# DSP.net
KiCad netlist of a schematic drawn in Altium Designer
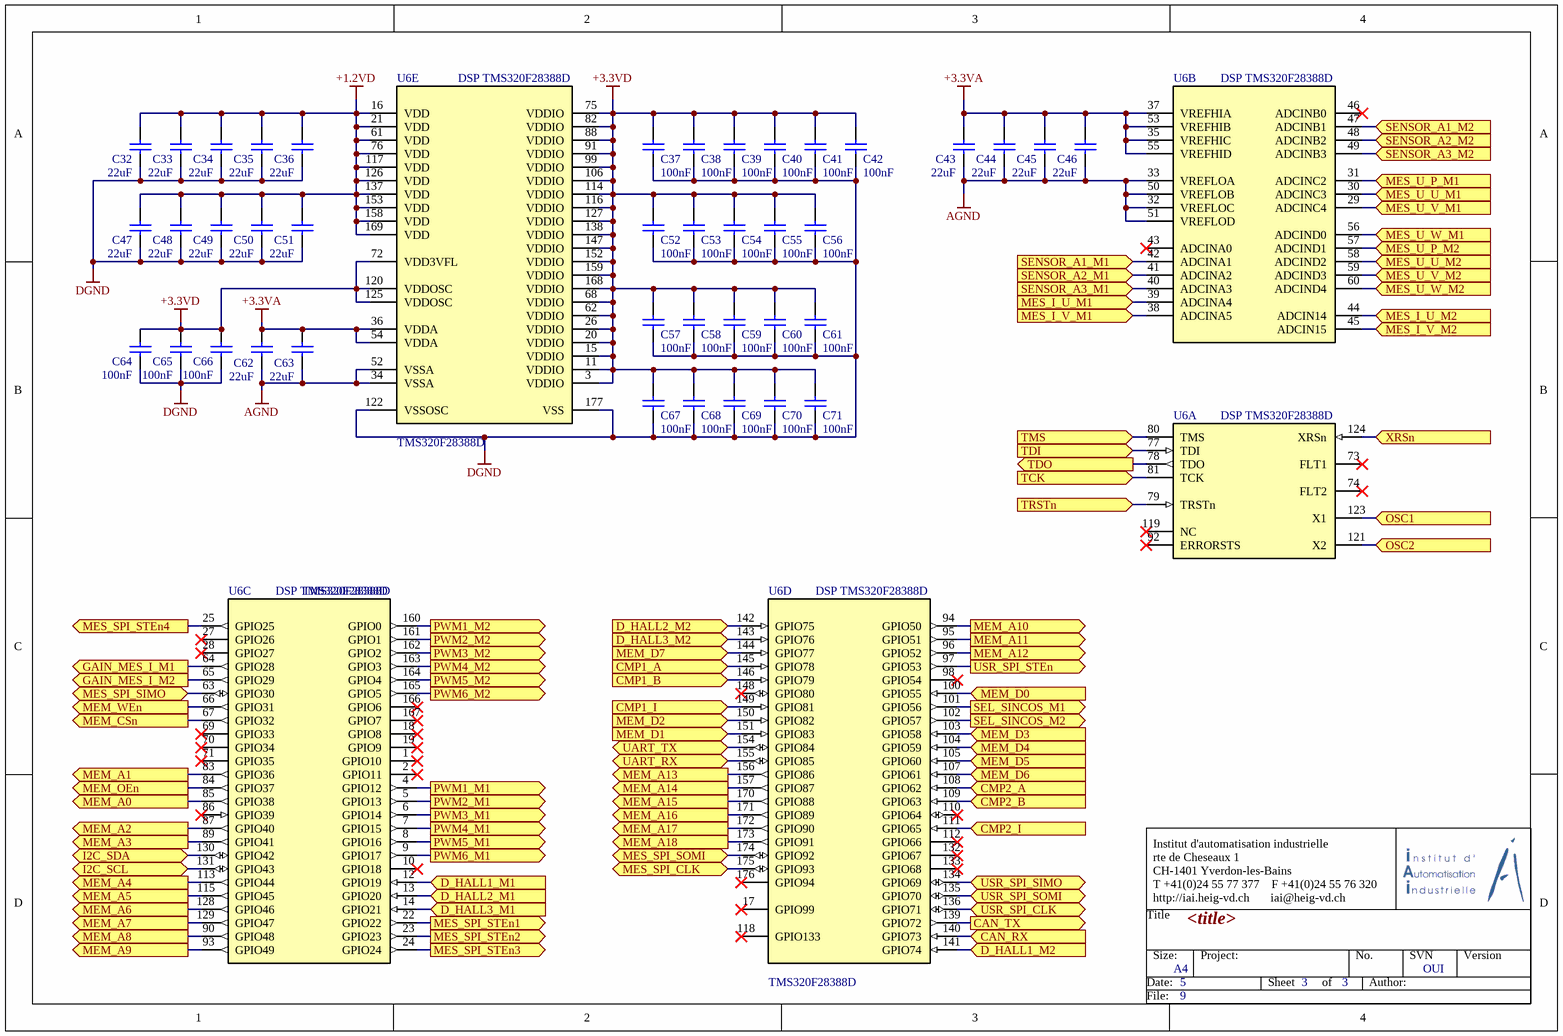
[diagram p0: DSP.SchDoc]

(export (version "E")
  (design (tool "Eeschema 10.0.6"))
  (components
    (comp (ref "C32")
      (value "22uF")
      (footprint "CommandBoard:CAPC1608X08N")
      (description "22µF ±20% 6,3V Condensateurs céramique X5R 0603 (1608 métrique)")
      (fields (field (name "Comment") "CAP CER 22uF 0603"))
      (libsource (lib "CommandBoard") (part "CAP CER 22uF 20% 6V3 0603"))
    )
    (comp (ref "C33")
      (value "22uF")
      (footprint "CommandBoard:CAPC1608X08N")
      (description "22µF ±20% 6,3V Condensateurs céramique X5R 0603 (1608 métrique)")
      (fields (field (name "Comment") "CAP CER 22uF 0603"))
      (libsource (lib "CommandBoard") (part "CAP CER 22uF 20% 6V3 0603"))
    )
    (comp (ref "C34")
      (value "22uF")
      (footprint "CommandBoard:CAPC1608X08N")
      (description "22µF ±20% 6,3V Condensateurs céramique X5R 0603 (1608 métrique)")
      (fields (field (name "Comment") "CAP CER 22uF 0603"))
      (libsource (lib "CommandBoard") (part "CAP CER 22uF 20% 6V3 0603"))
    )
    (comp (ref "C35")
      (value "22uF")
      (footprint "CommandBoard:CAPC1608X08N")
      (description "22µF ±20% 6,3V Condensateurs céramique X5R 0603 (1608 métrique)")
      (fields (field (name "Comment") "CAP CER 22uF 0603"))
      (libsource (lib "CommandBoard") (part "CAP CER 22uF 20% 6V3 0603"))
    )
    (comp (ref "C36")
      (value "22uF")
      (footprint "CommandBoard:CAPC1608X08N")
      (description "22µF ±20% 6,3V Condensateurs céramique X5R 0603 (1608 métrique)")
      (fields (field (name "Comment") "CAP CER 22uF 0603"))
      (libsource (lib "CommandBoard") (part "CAP CER 22uF 20% 6V3 0603"))
    )
    (comp (ref "C37")
      (value "100nF")
      (footprint "CommandBoard:CAPC1608X08N")
      (description "0,1µF ±10% 10V Condensateurs céramique X7R 0603 (1608 métrique)")
      (fields (field (name "Comment") "CAP CER 100nF 0603"))
      (libsource (lib "CommandBoard") (part "CAP CER 100nF 10% 10V 0603"))
    )
    (comp (ref "C38")
      (value "100nF")
      (footprint "CommandBoard:CAPC1608X08N")
      (description "0,1µF ±10% 10V Condensateurs céramique X7R 0603 (1608 métrique)")
      (fields (field (name "Comment") "CAP CER 100nF 0603"))
      (libsource (lib "CommandBoard") (part "CAP CER 100nF 10% 10V 0603"))
    )
    (comp (ref "C39")
      (value "100nF")
      (footprint "CommandBoard:CAPC1608X08N")
      (description "0,1µF ±10% 10V Condensateurs céramique X7R 0603 (1608 métrique)")
      (fields (field (name "Comment") "CAP CER 100nF 0603"))
      (libsource (lib "CommandBoard") (part "CAP CER 100nF 10% 10V 0603"))
    )
    (comp (ref "C40")
      (value "100nF")
      (footprint "CommandBoard:CAPC1608X08N")
      (description "0,1µF ±10% 10V Condensateurs céramique X7R 0603 (1608 métrique)")
      (fields (field (name "Comment") "CAP CER 100nF 0603"))
      (libsource (lib "CommandBoard") (part "CAP CER 100nF 10% 10V 0603"))
    )
    (comp (ref "C41")
      (value "100nF")
      (footprint "CommandBoard:CAPC1608X08N")
      (description "0,1µF ±10% 10V Condensateurs céramique X7R 0603 (1608 métrique)")
      (fields (field (name "Comment") "CAP CER 100nF 0603"))
      (libsource (lib "CommandBoard") (part "CAP CER 100nF 10% 10V 0603"))
    )
    (comp (ref "C42")
      (value "100nF")
      (footprint "CommandBoard:CAPC1608X08N")
      (description "0,1µF ±10% 10V Condensateurs céramique X7R 0603 (1608 métrique)")
      (fields (field (name "Comment") "CAP CER 100nF 0603"))
      (libsource (lib "CommandBoard") (part "CAP CER 100nF 10% 10V 0603"))
    )
    (comp (ref "C43")
      (value "22uF")
      (footprint "CommandBoard:CAPC1608X08N")
      (description "22µF ±20% 6,3V Condensateurs céramique X5R 0603 (1608 métrique)")
      (fields (field (name "Comment") "CAP CER 22uF 0603"))
      (libsource (lib "CommandBoard") (part "CAP CER 22uF 20% 6V3 0603"))
    )
    (comp (ref "C44")
      (value "22uF")
      (footprint "CommandBoard:CAPC1608X08N")
      (description "22µF ±20% 6,3V Condensateurs céramique X5R 0603 (1608 métrique)")
      (fields (field (name "Comment") "CAP CER 22uF 0603"))
      (libsource (lib "CommandBoard") (part "CAP CER 22uF 20% 6V3 0603"))
    )
    (comp (ref "C45")
      (value "22uF")
      (footprint "CommandBoard:CAPC1608X08N")
      (description "22µF ±20% 6,3V Condensateurs céramique X5R 0603 (1608 métrique)")
      (fields (field (name "Comment") "CAP CER 22uF 0603"))
      (libsource (lib "CommandBoard") (part "CAP CER 22uF 20% 6V3 0603"))
    )
    (comp (ref "C46")
      (value "22uF")
      (footprint "CommandBoard:CAPC1608X08N")
      (description "22µF ±20% 6,3V Condensateurs céramique X5R 0603 (1608 métrique)")
      (fields (field (name "Comment") "CAP CER 22uF 0603"))
      (libsource (lib "CommandBoard") (part "CAP CER 22uF 20% 6V3 0603"))
    )
    (comp (ref "C47")
      (value "22uF")
      (footprint "CommandBoard:CAPC1608X08N")
      (description "22µF ±20% 6,3V Condensateurs céramique X5R 0603 (1608 métrique)")
      (fields (field (name "Comment") "CAP CER 22uF 0603"))
      (libsource (lib "CommandBoard") (part "CAP CER 22uF 20% 6V3 0603"))
    )
    (comp (ref "C48")
      (value "22uF")
      (footprint "CommandBoard:CAPC1608X08N")
      (description "22µF ±20% 6,3V Condensateurs céramique X5R 0603 (1608 métrique)")
      (fields (field (name "Comment") "CAP CER 22uF 0603"))
      (libsource (lib "CommandBoard") (part "CAP CER 22uF 20% 6V3 0603"))
    )
    (comp (ref "C49")
      (value "22uF")
      (footprint "CommandBoard:CAPC1608X08N")
      (description "22µF ±20% 6,3V Condensateurs céramique X5R 0603 (1608 métrique)")
      (fields (field (name "Comment") "CAP CER 22uF 0603"))
      (libsource (lib "CommandBoard") (part "CAP CER 22uF 20% 6V3 0603"))
    )
    (comp (ref "C50")
      (value "22uF")
      (footprint "CommandBoard:CAPC1608X08N")
      (description "22µF ±20% 6,3V Condensateurs céramique X5R 0603 (1608 métrique)")
      (fields (field (name "Comment") "CAP CER 22uF 0603"))
      (libsource (lib "CommandBoard") (part "CAP CER 22uF 20% 6V3 0603"))
    )
    (comp (ref "C51")
      (value "22uF")
      (footprint "CommandBoard:CAPC1608X08N")
      (description "22µF ±20% 6,3V Condensateurs céramique X5R 0603 (1608 métrique)")
      (fields (field (name "Comment") "CAP CER 22uF 0603"))
      (libsource (lib "CommandBoard") (part "CAP CER 22uF 20% 6V3 0603"))
    )
    (comp (ref "C52")
      (value "100nF")
      (footprint "CommandBoard:CAPC1608X08N")
      (description "0,1µF ±10% 10V Condensateurs céramique X7R 0603 (1608 métrique)")
      (fields (field (name "Comment") "CAP CER 100nF 0603"))
      (libsource (lib "CommandBoard") (part "CAP CER 100nF 10% 10V 0603"))
    )
    (comp (ref "C53")
      (value "100nF")
      (footprint "CommandBoard:CAPC1608X08N")
      (description "0,1µF ±10% 10V Condensateurs céramique X7R 0603 (1608 métrique)")
      (fields (field (name "Comment") "CAP CER 100nF 0603"))
      (libsource (lib "CommandBoard") (part "CAP CER 100nF 10% 10V 0603"))
    )
    (comp (ref "C54")
      (value "100nF")
      (footprint "CommandBoard:CAPC1608X08N")
      (description "0,1µF ±10% 10V Condensateurs céramique X7R 0603 (1608 métrique)")
      (fields (field (name "Comment") "CAP CER 100nF 0603"))
      (libsource (lib "CommandBoard") (part "CAP CER 100nF 10% 10V 0603"))
    )
    (comp (ref "C55")
      (value "100nF")
      (footprint "CommandBoard:CAPC1608X08N")
      (description "0,1µF ±10% 10V Condensateurs céramique X7R 0603 (1608 métrique)")
      (fields (field (name "Comment") "CAP CER 100nF 0603"))
      (libsource (lib "CommandBoard") (part "CAP CER 100nF 10% 10V 0603"))
    )
    (comp (ref "C56")
      (value "100nF")
      (footprint "CommandBoard:CAPC1608X08N")
      (description "0,1µF ±10% 10V Condensateurs céramique X7R 0603 (1608 métrique)")
      (fields (field (name "Comment") "CAP CER 100nF 0603"))
      (libsource (lib "CommandBoard") (part "CAP CER 100nF 10% 10V 0603"))
    )
    (comp (ref "C57")
      (value "100nF")
      (footprint "CommandBoard:CAPC1608X08N")
      (description "0,1µF ±10% 10V Condensateurs céramique X7R 0603 (1608 métrique)")
      (fields (field (name "Comment") "CAP CER 100nF 0603"))
      (libsource (lib "CommandBoard") (part "CAP CER 100nF 10% 10V 0603"))
    )
    (comp (ref "C58")
      (value "100nF")
      (footprint "CommandBoard:CAPC1608X08N")
      (description "0,1µF ±10% 10V Condensateurs céramique X7R 0603 (1608 métrique)")
      (fields (field (name "Comment") "CAP CER 100nF 0603"))
      (libsource (lib "CommandBoard") (part "CAP CER 100nF 10% 10V 0603"))
    )
    (comp (ref "C59")
      (value "100nF")
      (footprint "CommandBoard:CAPC1608X08N")
      (description "0,1µF ±10% 10V Condensateurs céramique X7R 0603 (1608 métrique)")
      (fields (field (name "Comment") "CAP CER 100nF 0603"))
      (libsource (lib "CommandBoard") (part "CAP CER 100nF 10% 10V 0603"))
    )
    (comp (ref "C60")
      (value "100nF")
      (footprint "CommandBoard:CAPC1608X08N")
      (description "0,1µF ±10% 10V Condensateurs céramique X7R 0603 (1608 métrique)")
      (fields (field (name "Comment") "CAP CER 100nF 0603"))
      (libsource (lib "CommandBoard") (part "CAP CER 100nF 10% 10V 0603"))
    )
    (comp (ref "C61")
      (value "100nF")
      (footprint "CommandBoard:CAPC1608X08N")
      (description "0,1µF ±10% 10V Condensateurs céramique X7R 0603 (1608 métrique)")
      (fields (field (name "Comment") "CAP CER 100nF 0603"))
      (libsource (lib "CommandBoard") (part "CAP CER 100nF 10% 10V 0603"))
    )
    (comp (ref "C62")
      (value "22uF")
      (footprint "CommandBoard:CAPC1608X08N")
      (description "22µF ±20% 6,3V Condensateurs céramique X5R 0603 (1608 métrique)")
      (fields (field (name "Comment") "CAP CER 22uF 0603"))
      (libsource (lib "CommandBoard") (part "CAP CER 22uF 20% 6V3 0603"))
    )
    (comp (ref "C63")
      (value "22uF")
      (footprint "CommandBoard:CAPC1608X08N")
      (description "22µF ±20% 6,3V Condensateurs céramique X5R 0603 (1608 métrique)")
      (fields (field (name "Comment") "CAP CER 22uF 0603"))
      (libsource (lib "CommandBoard") (part "CAP CER 22uF 20% 6V3 0603"))
    )
    (comp (ref "C64")
      (value "100nF")
      (footprint "CommandBoard:CAPC1608X08N")
      (description "0,1µF ±10% 10V Condensateurs céramique X7R 0603 (1608 métrique)")
      (fields (field (name "Comment") "CAP CER 100nF 0603"))
      (libsource (lib "CommandBoard") (part "CAP CER 100nF 10% 10V 0603"))
    )
    (comp (ref "C65")
      (value "100nF")
      (footprint "CommandBoard:CAPC1608X08N")
      (description "0,1µF ±10% 10V Condensateurs céramique X7R 0603 (1608 métrique)")
      (fields (field (name "Comment") "CAP CER 100nF 0603"))
      (libsource (lib "CommandBoard") (part "CAP CER 100nF 10% 10V 0603"))
    )
    (comp (ref "C66")
      (value "100nF")
      (footprint "CommandBoard:CAPC1608X08N")
      (description "0,1µF ±10% 10V Condensateurs céramique X7R 0603 (1608 métrique)")
      (fields (field (name "Comment") "CAP CER 100nF 0603"))
      (libsource (lib "CommandBoard") (part "CAP CER 100nF 10% 10V 0603"))
    )
    (comp (ref "C67")
      (value "100nF")
      (footprint "CommandBoard:CAPC1608X08N")
      (description "0,1µF ±10% 10V Condensateurs céramique X7R 0603 (1608 métrique)")
      (fields (field (name "Comment") "CAP CER 100nF 0603"))
      (libsource (lib "CommandBoard") (part "CAP CER 100nF 10% 10V 0603"))
    )
    (comp (ref "C68")
      (value "100nF")
      (footprint "CommandBoard:CAPC1608X08N")
      (description "0,1µF ±10% 10V Condensateurs céramique X7R 0603 (1608 métrique)")
      (fields (field (name "Comment") "CAP CER 100nF 0603"))
      (libsource (lib "CommandBoard") (part "CAP CER 100nF 10% 10V 0603"))
    )
    (comp (ref "C69")
      (value "100nF")
      (footprint "CommandBoard:CAPC1608X08N")
      (description "0,1µF ±10% 10V Condensateurs céramique X7R 0603 (1608 métrique)")
      (fields (field (name "Comment") "CAP CER 100nF 0603"))
      (libsource (lib "CommandBoard") (part "CAP CER 100nF 10% 10V 0603"))
    )
    (comp (ref "C70")
      (value "100nF")
      (footprint "CommandBoard:CAPC1608X08N")
      (description "0,1µF ±10% 10V Condensateurs céramique X7R 0603 (1608 métrique)")
      (fields (field (name "Comment") "CAP CER 100nF 0603"))
      (libsource (lib "CommandBoard") (part "CAP CER 100nF 10% 10V 0603"))
    )
    (comp (ref "C71")
      (value "100nF")
      (footprint "CommandBoard:CAPC1608X08N")
      (description "0,1µF ±10% 10V Condensateurs céramique X7R 0603 (1608 métrique)")
      (fields (field (name "Comment") "CAP CER 100nF 0603"))
      (libsource (lib "CommandBoard") (part "CAP CER 100nF 10% 10V 0603"))
    )
    (comp (ref "U6")
      (value "DSP TMS320F28388D")
      (footprint "CommandBoard:TSQFP50P2600X2600X160_HS-177N")
      (fields (field (name "ALTIUM_VALUE") "TMS320F28388D"))
      (libsource (lib "") (part "DSP TMS320F28388D_2"))
    )
  )
  (nets
    (net (code "1") (name "+1.2VD") (class "Default")
      (node (ref "C32") (pin "2") (pinfunction "2_2") (pintype "passive"))
      (node (ref "C33") (pin "2") (pinfunction "2_2") (pintype "passive"))
      (node (ref "C34") (pin "2") (pinfunction "2_2") (pintype "passive"))
      (node (ref "C35") (pin "2") (pinfunction "2_2") (pintype "passive"))
      (node (ref "C36") (pin "2") (pinfunction "2_2") (pintype "passive"))
      (node (ref "C47") (pin "2") (pinfunction "2_2") (pintype "passive"))
      (node (ref "C48") (pin "2") (pinfunction "2_2") (pintype "passive"))
      (node (ref "C49") (pin "2") (pinfunction "2_2") (pintype "passive"))
      (node (ref "C50") (pin "2") (pinfunction "2_2") (pintype "passive"))
      (node (ref "C51") (pin "2") (pinfunction "2_2") (pintype "passive"))
      (node (ref "U6") (pin "117") (pinfunction "VDD_117") (pintype "power_in"))
      (node (ref "U6") (pin "126") (pinfunction "VDD_126") (pintype "power_in"))
      (node (ref "U6") (pin "137") (pinfunction "VDD_137") (pintype "power_in"))
      (node (ref "U6") (pin "153") (pinfunction "VDD_153") (pintype "power_in"))
      (node (ref "U6") (pin "158") (pinfunction "VDD_158") (pintype "power_in"))
      (node (ref "U6") (pin "16") (pinfunction "VDD_16") (pintype "power_in"))
      (node (ref "U6") (pin "169") (pinfunction "VDD_169") (pintype "power_in"))
      (node (ref "U6") (pin "21") (pinfunction "VDD_21") (pintype "power_in"))
      (node (ref "U6") (pin "61") (pinfunction "VDD_61") (pintype "power_in"))
      (node (ref "U6") (pin "76") (pinfunction "VDD_76") (pintype "power_in"))
    )
    (net (code "2") (name "+3.3VA") (class "Default")
      (node (ref "C43") (pin "2") (pinfunction "2_2") (pintype "passive"))
      (node (ref "C44") (pin "2") (pinfunction "2_2") (pintype "passive"))
      (node (ref "C45") (pin "2") (pinfunction "2_2") (pintype "passive"))
      (node (ref "C46") (pin "2") (pinfunction "2_2") (pintype "passive"))
      (node (ref "C62") (pin "2") (pinfunction "2_2") (pintype "passive"))
      (node (ref "C63") (pin "2") (pinfunction "2_2") (pintype "passive"))
      (node (ref "U6") (pin "35") (pinfunction "VREFHIC_35") (pintype "power_in"))
      (node (ref "U6") (pin "36") (pinfunction "VDDA_36") (pintype "power_in"))
      (node (ref "U6") (pin "37") (pinfunction "VREFHIA_37") (pintype "power_in"))
      (node (ref "U6") (pin "53") (pinfunction "VREFHIB_53") (pintype "power_in"))
      (node (ref "U6") (pin "54") (pinfunction "VDDA_54") (pintype "power_in"))
      (node (ref "U6") (pin "55") (pinfunction "VREFHID_55") (pintype "power_in"))
    )
    (net (code "3") (name "+3.3VD") (class "Default")
      (node (ref "C37") (pin "2") (pinfunction "2_2") (pintype "passive"))
      (node (ref "C38") (pin "2") (pinfunction "2_2") (pintype "passive"))
      (node (ref "C39") (pin "2") (pinfunction "2_2") (pintype "passive"))
      (node (ref "C40") (pin "2") (pinfunction "2_2") (pintype "passive"))
      (node (ref "C41") (pin "2") (pinfunction "2_2") (pintype "passive"))
      (node (ref "C42") (pin "2") (pinfunction "2_2") (pintype "passive"))
      (node (ref "C52") (pin "2") (pinfunction "2_2") (pintype "passive"))
      (node (ref "C53") (pin "2") (pinfunction "2_2") (pintype "passive"))
      (node (ref "C54") (pin "2") (pinfunction "2_2") (pintype "passive"))
      (node (ref "C55") (pin "2") (pinfunction "2_2") (pintype "passive"))
      (node (ref "C56") (pin "2") (pinfunction "2_2") (pintype "passive"))
      (node (ref "C57") (pin "2") (pinfunction "2_2") (pintype "passive"))
      (node (ref "C58") (pin "2") (pinfunction "2_2") (pintype "passive"))
      (node (ref "C59") (pin "2") (pinfunction "2_2") (pintype "passive"))
      (node (ref "C60") (pin "2") (pinfunction "2_2") (pintype "passive"))
      (node (ref "C61") (pin "2") (pinfunction "2_2") (pintype "passive"))
      (node (ref "C64") (pin "2") (pinfunction "2_2") (pintype "passive"))
      (node (ref "C65") (pin "2") (pinfunction "2_2") (pintype "passive"))
      (node (ref "C66") (pin "2") (pinfunction "2_2") (pintype "passive"))
      (node (ref "C67") (pin "2") (pinfunction "2_2") (pintype "passive"))
      (node (ref "C68") (pin "2") (pinfunction "2_2") (pintype "passive"))
      (node (ref "C69") (pin "2") (pinfunction "2_2") (pintype "passive"))
      (node (ref "C70") (pin "2") (pinfunction "2_2") (pintype "passive"))
      (node (ref "C71") (pin "2") (pinfunction "2_2") (pintype "passive"))
      (node (ref "U6") (pin "106") (pinfunction "VDDIO_106") (pintype "power_in"))
      (node (ref "U6") (pin "11") (pinfunction "VDDIO_11") (pintype "power_in"))
      (node (ref "U6") (pin "114") (pinfunction "VDDIO_114") (pintype "power_in"))
      (node (ref "U6") (pin "116") (pinfunction "VDDIO_116") (pintype "power_in"))
      (node (ref "U6") (pin "120") (pinfunction "VDDOSC_120") (pintype "power_in"))
      (node (ref "U6") (pin "125") (pinfunction "VDDOSC_125") (pintype "power_in"))
      (node (ref "U6") (pin "127") (pinfunction "VDDIO_127") (pintype "power_in"))
      (node (ref "U6") (pin "138") (pinfunction "VDDIO_138") (pintype "power_in"))
      (node (ref "U6") (pin "147") (pinfunction "VDDIO_147") (pintype "power_in"))
      (node (ref "U6") (pin "15") (pinfunction "VDDIO_15") (pintype "power_in"))
      (node (ref "U6") (pin "152") (pinfunction "VDDIO_152") (pintype "power_in"))
      (node (ref "U6") (pin "159") (pinfunction "VDDIO_159") (pintype "power_in"))
      (node (ref "U6") (pin "168") (pinfunction "VDDIO_168") (pintype "power_in"))
      (node (ref "U6") (pin "20") (pinfunction "VDDIO_20") (pintype "power_in"))
      (node (ref "U6") (pin "26") (pinfunction "VDDIO_26") (pintype "power_in"))
      (node (ref "U6") (pin "3") (pinfunction "VDDIO_3") (pintype "power_in"))
      (node (ref "U6") (pin "62") (pinfunction "VDDIO_62") (pintype "power_in"))
      (node (ref "U6") (pin "68") (pinfunction "VDDIO_68") (pintype "power_in"))
      (node (ref "U6") (pin "72") (pinfunction "VDD3VFL_72") (pintype "power_in"))
      (node (ref "U6") (pin "75") (pinfunction "VDDIO_75") (pintype "power_in"))
      (node (ref "U6") (pin "82") (pinfunction "VDDIO_82") (pintype "power_in"))
      (node (ref "U6") (pin "88") (pinfunction "VDDIO_88") (pintype "power_in"))
      (node (ref "U6") (pin "91") (pinfunction "VDDIO_91") (pintype "power_in"))
      (node (ref "U6") (pin "99") (pinfunction "VDDIO_99") (pintype "power_in"))
    )
    (net (code "4") (name "/CAN_RX") (class "Default")
      (node (ref "U6") (pin "140") (pinfunction "GPIO73_140") (pintype "input"))
    )
    (net (code "5") (name "/CAN_TX") (class "Default")
      (node (ref "U6") (pin "139") (pinfunction "GPIO72_139") (pintype "output"))
    )
    (net (code "6") (name "/CMP1_A") (class "Default")
      (node (ref "U6") (pin "145") (pinfunction "GPIO78_145") (pintype "input"))
    )
    (net (code "7") (name "/CMP1_B") (class "Default")
      (node (ref "U6") (pin "146") (pinfunction "GPIO79_146") (pintype "input"))
    )
    (net (code "8") (name "/CMP1_I") (class "Default")
      (node (ref "U6") (pin "149") (pinfunction "GPIO81_149") (pintype "input"))
    )
    (net (code "9") (name "/CMP2_A") (class "Default")
      (node (ref "U6") (pin "108") (pinfunction "GPIO62_108") (pintype "input"))
    )
    (net (code "10") (name "/CMP2_B") (class "Default")
      (node (ref "U6") (pin "109") (pinfunction "GPIO63_109") (pintype "input"))
    )
    (net (code "11") (name "/CMP2_I") (class "Default")
      (node (ref "U6") (pin "111") (pinfunction "GPIO65_111") (pintype "input"))
    )
    (net (code "12") (name "/D_HALL1_M1") (class "Default")
      (node (ref "U6") (pin "12") (pinfunction "GPIO19_12") (pintype "input"))
    )
    (net (code "13") (name "/D_HALL1_M2") (class "Default")
      (node (ref "U6") (pin "141") (pinfunction "GPIO74_141") (pintype "input"))
    )
    (net (code "14") (name "/D_HALL2_M1") (class "Default")
      (node (ref "U6") (pin "13") (pinfunction "GPIO20_13") (pintype "input"))
    )
    (net (code "15") (name "/D_HALL2_M2") (class "Default")
      (node (ref "U6") (pin "142") (pinfunction "GPIO75_142") (pintype "input"))
    )
    (net (code "16") (name "/D_HALL3_M1") (class "Default")
      (node (ref "U6") (pin "14") (pinfunction "GPIO21_14") (pintype "input"))
    )
    (net (code "17") (name "/D_HALL3_M2") (class "Default")
      (node (ref "U6") (pin "143") (pinfunction "GPIO76_143") (pintype "input"))
    )
    (net (code "18") (name "/GAIN_MES_I_M1") (class "Default")
      (node (ref "U6") (pin "64") (pinfunction "GPIO28_64") (pintype "output"))
    )
    (net (code "19") (name "/GAIN_MES_I_M2") (class "Default")
      (node (ref "U6") (pin "65") (pinfunction "GPIO29_65") (pintype "output"))
    )
    (net (code "20") (name "/I2C_SCL") (class "Default")
      (node (ref "U6") (pin "131") (pinfunction "GPIO43_131") (pintype "bidirectional"))
    )
    (net (code "21") (name "/I2C_SDA") (class "Default")
      (node (ref "U6") (pin "130") (pinfunction "GPIO42_130") (pintype "bidirectional"))
    )
    (net (code "22") (name "/MEM_A0") (class "Default")
      (node (ref "U6") (pin "85") (pinfunction "GPIO38_85") (pintype "output"))
    )
    (net (code "23") (name "/MEM_A1") (class "Default")
      (node (ref "U6") (pin "83") (pinfunction "GPIO36_83") (pintype "output"))
    )
    (net (code "24") (name "/MEM_A2") (class "Default")
      (node (ref "U6") (pin "87") (pinfunction "GPIO40_87") (pintype "output"))
    )
    (net (code "25") (name "/MEM_A3") (class "Default")
      (node (ref "U6") (pin "89") (pinfunction "GPIO41_89") (pintype "output"))
    )
    (net (code "26") (name "/MEM_A4") (class "Default")
      (node (ref "U6") (pin "113") (pinfunction "GPIO44_113") (pintype "output"))
    )
    (net (code "27") (name "/MEM_A5") (class "Default")
      (node (ref "U6") (pin "115") (pinfunction "GPIO45_115") (pintype "output"))
    )
    (net (code "28") (name "/MEM_A6") (class "Default")
      (node (ref "U6") (pin "128") (pinfunction "GPIO46_128") (pintype "output"))
    )
    (net (code "29") (name "/MEM_A7") (class "Default")
      (node (ref "U6") (pin "129") (pinfunction "GPIO47_129") (pintype "output"))
    )
    (net (code "30") (name "/MEM_A8") (class "Default")
      (node (ref "U6") (pin "90") (pinfunction "GPIO48_90") (pintype "output"))
    )
    (net (code "31") (name "/MEM_A9") (class "Default")
      (node (ref "U6") (pin "93") (pinfunction "GPIO49_93") (pintype "output"))
    )
    (net (code "32") (name "/MEM_A10") (class "Default")
      (node (ref "U6") (pin "94") (pinfunction "GPIO50_94") (pintype "output"))
    )
    (net (code "33") (name "/MEM_A11") (class "Default")
      (node (ref "U6") (pin "95") (pinfunction "GPIO51_95") (pintype "output"))
    )
    (net (code "34") (name "/MEM_A12") (class "Default")
      (node (ref "U6") (pin "96") (pinfunction "GPIO52_96") (pintype "output"))
    )
    (net (code "35") (name "/MEM_A13") (class "Default")
      (node (ref "U6") (pin "156") (pinfunction "GPIO86_156") (pintype "output"))
    )
    (net (code "36") (name "/MEM_A14") (class "Default")
      (node (ref "U6") (pin "157") (pinfunction "GPIO87_157") (pintype "output"))
    )
    (net (code "37") (name "/MEM_A15") (class "Default")
      (node (ref "U6") (pin "170") (pinfunction "GPIO88_170") (pintype "output"))
    )
    (net (code "38") (name "/MEM_A16") (class "Default")
      (node (ref "U6") (pin "171") (pinfunction "GPIO89_171") (pintype "output"))
    )
    (net (code "39") (name "/MEM_A17") (class "Default")
      (node (ref "U6") (pin "172") (pinfunction "GPIO90_172") (pintype "output"))
    )
    (net (code "40") (name "/MEM_A18") (class "Default")
      (node (ref "U6") (pin "173") (pinfunction "GPIO91_173") (pintype "output"))
    )
    (net (code "41") (name "/MEM_CSn") (class "Default")
      (node (ref "U6") (pin "67") (pinfunction "GPIO32_67") (pintype "output"))
    )
    (net (code "42") (name "/MEM_D0") (class "Default")
      (node (ref "U6") (pin "100") (pinfunction "GPIO55_100") (pintype "input"))
    )
    (net (code "43") (name "/MEM_D1") (class "Default")
      (node (ref "U6") (pin "151") (pinfunction "GPIO83_151") (pintype "input"))
    )
    (net (code "44") (name "/MEM_D2") (class "Default")
      (node (ref "U6") (pin "150") (pinfunction "GPIO82_150") (pintype "input"))
    )
    (net (code "45") (name "/MEM_D3") (class "Default")
      (node (ref "U6") (pin "103") (pinfunction "GPIO58_103") (pintype "input"))
    )
    (net (code "46") (name "/MEM_D4") (class "Default")
      (node (ref "U6") (pin "104") (pinfunction "GPIO59_104") (pintype "input"))
    )
    (net (code "47") (name "/MEM_D5") (class "Default")
      (node (ref "U6") (pin "105") (pinfunction "GPIO60_105") (pintype "input"))
    )
    (net (code "48") (name "/MEM_D6") (class "Default")
      (node (ref "U6") (pin "107") (pinfunction "GPIO61_107") (pintype "input"))
    )
    (net (code "49") (name "/MEM_D7") (class "Default")
      (node (ref "U6") (pin "144") (pinfunction "GPIO77_144") (pintype "input"))
    )
    (net (code "50") (name "/MEM_OEn") (class "Default")
      (node (ref "U6") (pin "84") (pinfunction "GPIO37_84") (pintype "output"))
    )
    (net (code "51") (name "/MEM_WEn") (class "Default")
      (node (ref "U6") (pin "66") (pinfunction "GPIO31_66") (pintype "output"))
    )
    (net (code "52") (name "/MES_I_U_M1") (class "Default")
      (node (ref "U6") (pin "39") (pinfunction "ADCINA4_39") (pintype "passive"))
    )
    (net (code "53") (name "/MES_I_U_M2") (class "Default")
      (node (ref "U6") (pin "44") (pinfunction "ADCIN14_44") (pintype "passive"))
    )
    (net (code "54") (name "/MES_I_V_M1") (class "Default")
      (node (ref "U6") (pin "38") (pinfunction "ADCINA5_38") (pintype "passive"))
    )
    (net (code "55") (name "/MES_I_V_M2") (class "Default")
      (node (ref "U6") (pin "45") (pinfunction "ADCIN15_45") (pintype "passive"))
    )
    (net (code "56") (name "/MES_SPI_CLK") (class "Default")
      (node (ref "U6") (pin "175") (pinfunction "GPIO93_175") (pintype "bidirectional"))
    )
    (net (code "57") (name "/MES_SPI_SIMO") (class "Default")
      (node (ref "U6") (pin "63") (pinfunction "GPIO30_63") (pintype "bidirectional"))
    )
    (net (code "58") (name "/MES_SPI_SOMI") (class "Default")
      (node (ref "U6") (pin "174") (pinfunction "GPIO92_174") (pintype "bidirectional"))
    )
    (net (code "59") (name "/MES_SPI_STEn1") (class "Default")
      (node (ref "U6") (pin "22") (pinfunction "GPIO22_22") (pintype "output"))
    )
    (net (code "60") (name "/MES_SPI_STEn2") (class "Default")
      (node (ref "U6") (pin "23") (pinfunction "GPIO23_23") (pintype "output"))
    )
    (net (code "61") (name "/MES_SPI_STEn3") (class "Default")
      (node (ref "U6") (pin "24") (pinfunction "GPIO24_24") (pintype "output"))
    )
    (net (code "62") (name "/MES_SPI_STEn4") (class "Default")
      (node (ref "U6") (pin "25") (pinfunction "GPIO25_25") (pintype "output"))
    )
    (net (code "63") (name "/MES_U_P_M1") (class "Default")
      (node (ref "U6") (pin "31") (pinfunction "ADCINC2_31") (pintype "passive"))
    )
    (net (code "64") (name "/MES_U_P_M2") (class "Default")
      (node (ref "U6") (pin "57") (pinfunction "ADCIND1_57") (pintype "passive"))
    )
    (net (code "65") (name "/MES_U_U_M1") (class "Default")
      (node (ref "U6") (pin "30") (pinfunction "ADCINC3_30") (pintype "passive"))
    )
    (net (code "66") (name "/MES_U_U_M2") (class "Default")
      (node (ref "U6") (pin "58") (pinfunction "ADCIND2_58") (pintype "passive"))
    )
    (net (code "67") (name "/MES_U_V_M1") (class "Default")
      (node (ref "U6") (pin "29") (pinfunction "ADCINC4_29") (pintype "passive"))
    )
    (net (code "68") (name "/MES_U_V_M2") (class "Default")
      (node (ref "U6") (pin "59") (pinfunction "ADCIND3_59") (pintype "passive"))
    )
    (net (code "69") (name "/MES_U_W_M1") (class "Default")
      (node (ref "U6") (pin "56") (pinfunction "ADCIND0_56") (pintype "passive"))
    )
    (net (code "70") (name "/MES_U_W_M2") (class "Default")
      (node (ref "U6") (pin "60") (pinfunction "ADCIND4_60") (pintype "passive"))
    )
    (net (code "71") (name "/OSC1") (class "Default")
      (node (ref "U6") (pin "123") (pinfunction "X1_123") (pintype "passive"))
    )
    (net (code "72") (name "/OSC2") (class "Default")
      (node (ref "U6") (pin "121") (pinfunction "X2_121") (pintype "passive"))
    )
    (net (code "73") (name "/PWM1_M1") (class "Default")
      (node (ref "U6") (pin "4") (pinfunction "GPIO12_4") (pintype "output"))
    )
    (net (code "74") (name "/PWM1_M2") (class "Default")
      (node (ref "U6") (pin "160") (pinfunction "GPIO0_160") (pintype "output"))
    )
    (net (code "75") (name "/PWM2_M1") (class "Default")
      (node (ref "U6") (pin "5") (pinfunction "GPIO13_5") (pintype "output"))
    )
    (net (code "76") (name "/PWM2_M2") (class "Default")
      (node (ref "U6") (pin "161") (pinfunction "GPIO1_161") (pintype "output"))
    )
    (net (code "77") (name "/PWM3_M1") (class "Default")
      (node (ref "U6") (pin "6") (pinfunction "GPIO14_6") (pintype "output"))
    )
    (net (code "78") (name "/PWM3_M2") (class "Default")
      (node (ref "U6") (pin "162") (pinfunction "GPIO2_162") (pintype "output"))
    )
    (net (code "79") (name "/PWM4_M1") (class "Default")
      (node (ref "U6") (pin "7") (pinfunction "GPIO15_7") (pintype "output"))
    )
    (net (code "80") (name "/PWM4_M2") (class "Default")
      (node (ref "U6") (pin "163") (pinfunction "GPIO3_163") (pintype "output"))
    )
    (net (code "81") (name "/PWM5_M1") (class "Default")
      (node (ref "U6") (pin "8") (pinfunction "GPIO16_8") (pintype "output"))
    )
    (net (code "82") (name "/PWM5_M2") (class "Default")
      (node (ref "U6") (pin "164") (pinfunction "GPIO4_164") (pintype "output"))
    )
    (net (code "83") (name "/PWM6_M1") (class "Default")
      (node (ref "U6") (pin "9") (pinfunction "GPIO17_9") (pintype "output"))
    )
    (net (code "84") (name "/PWM6_M2") (class "Default")
      (node (ref "U6") (pin "165") (pinfunction "GPIO5_165") (pintype "output"))
    )
    (net (code "85") (name "/SEL_SINCOS_M1") (class "Default")
      (node (ref "U6") (pin "101") (pinfunction "GPIO56_101") (pintype "output"))
    )
    (net (code "86") (name "/SEL_SINCOS_M2") (class "Default")
      (node (ref "U6") (pin "102") (pinfunction "GPIO57_102") (pintype "output"))
    )
    (net (code "87") (name "/SENSOR_A1_M1") (class "Default")
      (node (ref "U6") (pin "42") (pinfunction "ADCINA1_42") (pintype "passive"))
    )
    (net (code "88") (name "/SENSOR_A1_M2") (class "Default")
      (node (ref "U6") (pin "47") (pinfunction "ADCINB1_47") (pintype "passive"))
    )
    (net (code "89") (name "/SENSOR_A2_M1") (class "Default")
      (node (ref "U6") (pin "41") (pinfunction "ADCINA2_41") (pintype "passive"))
    )
    (net (code "90") (name "/SENSOR_A2_M2") (class "Default")
      (node (ref "U6") (pin "48") (pinfunction "ADCINB2_48") (pintype "passive"))
    )
    (net (code "91") (name "/SENSOR_A3_M1") (class "Default")
      (node (ref "U6") (pin "40") (pinfunction "ADCINA3_40") (pintype "passive"))
    )
    (net (code "92") (name "/SENSOR_A3_M2") (class "Default")
      (node (ref "U6") (pin "49") (pinfunction "ADCINB3_49") (pintype "passive"))
    )
    (net (code "93") (name "/TCK") (class "Default")
      (node (ref "U6") (pin "81") (pinfunction "TCK_81") (pintype "passive"))
    )
    (net (code "94") (name "/TDI") (class "Default")
      (node (ref "U6") (pin "77") (pinfunction "TDI_77") (pintype "input"))
    )
    (net (code "95") (name "/TDO") (class "Default")
      (node (ref "U6") (pin "78") (pinfunction "TDO_78") (pintype "output"))
    )
    (net (code "96") (name "/TMS") (class "Default")
      (node (ref "U6") (pin "80") (pinfunction "TMS_80") (pintype "passive"))
    )
    (net (code "97") (name "/TRSTn") (class "Default")
      (node (ref "U6") (pin "79") (pinfunction "TRST_N_79") (pintype "input"))
    )
    (net (code "98") (name "/UART_RX") (class "Default")
      (node (ref "U6") (pin "155") (pinfunction "GPIO85_155") (pintype "bidirectional"))
    )
    (net (code "99") (name "/UART_TX") (class "Default")
      (node (ref "U6") (pin "154") (pinfunction "GPIO84_154") (pintype "bidirectional"))
    )
    (net (code "100") (name "/USR_SPI_CLK") (class "Default")
      (node (ref "U6") (pin "136") (pinfunction "GPIO71_136") (pintype "bidirectional"))
    )
    (net (code "101") (name "/USR_SPI_SIMO") (class "Default")
      (node (ref "U6") (pin "134") (pinfunction "GPIO69_134") (pintype "bidirectional"))
    )
    (net (code "102") (name "/USR_SPI_SOMI") (class "Default")
      (node (ref "U6") (pin "135") (pinfunction "GPIO70_135") (pintype "bidirectional"))
    )
    (net (code "103") (name "/USR_SPI_STEn") (class "Default")
      (node (ref "U6") (pin "97") (pinfunction "GPIO53_97") (pintype "output"))
    )
    (net (code "104") (name "/XRSn") (class "Default")
      (node (ref "U6") (pin "124") (pinfunction "XRS_N_124") (pintype "input"))
    )
    (net (code "105") (name "AGND") (class "Default")
      (node (ref "C43") (pin "1") (pinfunction "1_1") (pintype "passive"))
      (node (ref "C44") (pin "1") (pinfunction "1_1") (pintype "passive"))
      (node (ref "C45") (pin "1") (pinfunction "1_1") (pintype "passive"))
      (node (ref "C46") (pin "1") (pinfunction "1_1") (pintype "passive"))
      (node (ref "C62") (pin "1") (pinfunction "1_1") (pintype "passive"))
      (node (ref "C63") (pin "1") (pinfunction "1_1") (pintype "passive"))
      (node (ref "U6") (pin "32") (pinfunction "VREFLOC_32") (pintype "power_in"))
      (node (ref "U6") (pin "33") (pinfunction "VREFLOA_33") (pintype "power_in"))
      (node (ref "U6") (pin "34") (pinfunction "VSSA_34") (pintype "power_in"))
      (node (ref "U6") (pin "50") (pinfunction "VREFLOB_50") (pintype "power_in"))
      (node (ref "U6") (pin "51") (pinfunction "VREFLOD_51") (pintype "power_in"))
      (node (ref "U6") (pin "52") (pinfunction "VSSA_52") (pintype "power_in"))
    )
    (net (code "106") (name "DGND") (class "Default")
      (node (ref "C32") (pin "1") (pinfunction "1_1") (pintype "passive"))
      (node (ref "C33") (pin "1") (pinfunction "1_1") (pintype "passive"))
      (node (ref "C34") (pin "1") (pinfunction "1_1") (pintype "passive"))
      (node (ref "C35") (pin "1") (pinfunction "1_1") (pintype "passive"))
      (node (ref "C36") (pin "1") (pinfunction "1_1") (pintype "passive"))
      (node (ref "C37") (pin "1") (pinfunction "1_1") (pintype "passive"))
      (node (ref "C38") (pin "1") (pinfunction "1_1") (pintype "passive"))
      (node (ref "C39") (pin "1") (pinfunction "1_1") (pintype "passive"))
      (node (ref "C40") (pin "1") (pinfunction "1_1") (pintype "passive"))
      (node (ref "C41") (pin "1") (pinfunction "1_1") (pintype "passive"))
      (node (ref "C42") (pin "1") (pinfunction "1_1") (pintype "passive"))
      (node (ref "C47") (pin "1") (pinfunction "1_1") (pintype "passive"))
      (node (ref "C48") (pin "1") (pinfunction "1_1") (pintype "passive"))
      (node (ref "C49") (pin "1") (pinfunction "1_1") (pintype "passive"))
      (node (ref "C50") (pin "1") (pinfunction "1_1") (pintype "passive"))
      (node (ref "C51") (pin "1") (pinfunction "1_1") (pintype "passive"))
      (node (ref "C52") (pin "1") (pinfunction "1_1") (pintype "passive"))
      (node (ref "C53") (pin "1") (pinfunction "1_1") (pintype "passive"))
      (node (ref "C54") (pin "1") (pinfunction "1_1") (pintype "passive"))
      (node (ref "C55") (pin "1") (pinfunction "1_1") (pintype "passive"))
      (node (ref "C56") (pin "1") (pinfunction "1_1") (pintype "passive"))
      (node (ref "C57") (pin "1") (pinfunction "1_1") (pintype "passive"))
      (node (ref "C58") (pin "1") (pinfunction "1_1") (pintype "passive"))
      (node (ref "C59") (pin "1") (pinfunction "1_1") (pintype "passive"))
      (node (ref "C60") (pin "1") (pinfunction "1_1") (pintype "passive"))
      (node (ref "C61") (pin "1") (pinfunction "1_1") (pintype "passive"))
      (node (ref "C64") (pin "1") (pinfunction "1_1") (pintype "passive"))
      (node (ref "C65") (pin "1") (pinfunction "1_1") (pintype "passive"))
      (node (ref "C66") (pin "1") (pinfunction "1_1") (pintype "passive"))
      (node (ref "C67") (pin "1") (pinfunction "1_1") (pintype "passive"))
      (node (ref "C68") (pin "1") (pinfunction "1_1") (pintype "passive"))
      (node (ref "C69") (pin "1") (pinfunction "1_1") (pintype "passive"))
      (node (ref "C70") (pin "1") (pinfunction "1_1") (pintype "passive"))
      (node (ref "C71") (pin "1") (pinfunction "1_1") (pintype "passive"))
      (node (ref "U6") (pin "122") (pinfunction "VSSOSC_122") (pintype "power_in"))
      (node (ref "U6") (pin "177") (pinfunction "VSS_177") (pintype "power_in"))
    )
    (net (code "107") (name "unconnected-(U6A-ERRORSTS-Pad92)") (class "Default")
      (node (ref "U6") (pin "92") (pinfunction "ERRORSTS_92") (pintype "passive+no_connect"))
    )
    (net (code "108") (name "unconnected-(U6A-FLT1-Pad73)") (class "Default")
      (node (ref "U6") (pin "73") (pinfunction "FLT1_73") (pintype "passive+no_connect"))
    )
    (net (code "109") (name "unconnected-(U6A-FLT2-Pad74)") (class "Default")
      (node (ref "U6") (pin "74") (pinfunction "FLT2_74") (pintype "passive+no_connect"))
    )
    (net (code "110") (name "unconnected-(U6A-NC-Pad119)") (class "Default")
      (node (ref "U6") (pin "119") (pinfunction "NC_119") (pintype "passive+no_connect"))
    )
    (net (code "111") (name "unconnected-(U6B-ADCINA0-Pad43)") (class "Default")
      (node (ref "U6") (pin "43") (pinfunction "ADCINA0_43") (pintype "passive+no_connect"))
    )
    (net (code "112") (name "unconnected-(U6B-ADCINB0-Pad46)") (class "Default")
      (node (ref "U6") (pin "46") (pinfunction "ADCINB0_46") (pintype "passive+no_connect"))
    )
    (net (code "113") (name "unconnected-(U6C-GPIO6-Pad166)") (class "Default")
      (node (ref "U6") (pin "166") (pinfunction "GPIO6_166") (pintype "passive+no_connect"))
    )
    (net (code "114") (name "unconnected-(U6C-GPIO7-Pad167)") (class "Default")
      (node (ref "U6") (pin "167") (pinfunction "GPIO7_167") (pintype "passive+no_connect"))
    )
    (net (code "115") (name "unconnected-(U6C-GPIO8-Pad18)") (class "Default")
      (node (ref "U6") (pin "18") (pinfunction "GPIO8_18") (pintype "passive+no_connect"))
    )
    (net (code "116") (name "unconnected-(U6C-GPIO9-Pad19)") (class "Default")
      (node (ref "U6") (pin "19") (pinfunction "GPIO9_19") (pintype "passive+no_connect"))
    )
    (net (code "117") (name "unconnected-(U6C-GPIO10-Pad1)") (class "Default")
      (node (ref "U6") (pin "1") (pinfunction "GPIO10_1") (pintype "passive+no_connect"))
    )
    (net (code "118") (name "unconnected-(U6C-GPIO11-Pad2)") (class "Default")
      (node (ref "U6") (pin "2") (pinfunction "GPIO11_2") (pintype "passive+no_connect"))
    )
    (net (code "119") (name "unconnected-(U6C-GPIO18-Pad10)") (class "Default")
      (node (ref "U6") (pin "10") (pinfunction "GPIO18_10") (pintype "passive+no_connect"))
    )
    (net (code "120") (name "unconnected-(U6C-GPIO26-Pad27)") (class "Default")
      (node (ref "U6") (pin "27") (pinfunction "GPIO26_27") (pintype "passive+no_connect"))
    )
    (net (code "121") (name "unconnected-(U6C-GPIO27-Pad28)") (class "Default")
      (node (ref "U6") (pin "28") (pinfunction "GPIO27_28") (pintype "passive+no_connect"))
    )
    (net (code "122") (name "unconnected-(U6C-GPIO33-Pad69)") (class "Default")
      (node (ref "U6") (pin "69") (pinfunction "GPIO33_69") (pintype "passive+no_connect"))
    )
    (net (code "123") (name "unconnected-(U6C-GPIO34-Pad70)") (class "Default")
      (node (ref "U6") (pin "70") (pinfunction "GPIO34_70") (pintype "passive+no_connect"))
    )
    (net (code "124") (name "unconnected-(U6C-GPIO35-Pad71)") (class "Default")
      (node (ref "U6") (pin "71") (pinfunction "GPIO35_71") (pintype "passive+no_connect"))
    )
    (net (code "125") (name "unconnected-(U6C-GPIO39-Pad86)") (class "Default")
      (node (ref "U6") (pin "86") (pinfunction "GPIO39_86") (pintype "input+no_connect"))
    )
    (net (code "126") (name "unconnected-(U6D-GPIO54-Pad98)") (class "Default")
      (node (ref "U6") (pin "98") (pinfunction "GPIO54_98") (pintype "passive+no_connect"))
    )
    (net (code "127") (name "unconnected-(U6D-GPIO64-Pad110)") (class "Default")
      (node (ref "U6") (pin "110") (pinfunction "GPIO64_110") (pintype "bidirectional+no_connect"))
    )
    (net (code "128") (name "unconnected-(U6D-GPIO66-Pad112)") (class "Default")
      (node (ref "U6") (pin "112") (pinfunction "GPIO66_112") (pintype "passive+no_connect"))
    )
    (net (code "129") (name "unconnected-(U6D-GPIO67-Pad132)") (class "Default")
      (node (ref "U6") (pin "132") (pinfunction "GPIO67_132") (pintype "passive+no_connect"))
    )
    (net (code "130") (name "unconnected-(U6D-GPIO68-Pad133)") (class "Default")
      (node (ref "U6") (pin "133") (pinfunction "GPIO68_133") (pintype "passive+no_connect"))
    )
    (net (code "131") (name "unconnected-(U6D-GPIO80-Pad148)") (class "Default")
      (node (ref "U6") (pin "148") (pinfunction "GPIO80_148") (pintype "bidirectional+no_connect"))
    )
    (net (code "132") (name "unconnected-(U6D-GPIO94-Pad176)") (class "Default")
      (node (ref "U6") (pin "176") (pinfunction "GPIO94_176") (pintype "passive+no_connect"))
    )
    (net (code "133") (name "unconnected-(U6D-GPIO99-Pad17)") (class "Default")
      (node (ref "U6") (pin "17") (pinfunction "GPIO99_17") (pintype "passive+no_connect"))
    )
    (net (code "134") (name "unconnected-(U6D-GPIO133-Pad118)") (class "Default")
      (node (ref "U6") (pin "118") (pinfunction "GPIO133_118") (pintype "passive+no_connect"))
    )
  )
)
